# controller.net
KiCad netlist of a schematic drawn in EAGLE
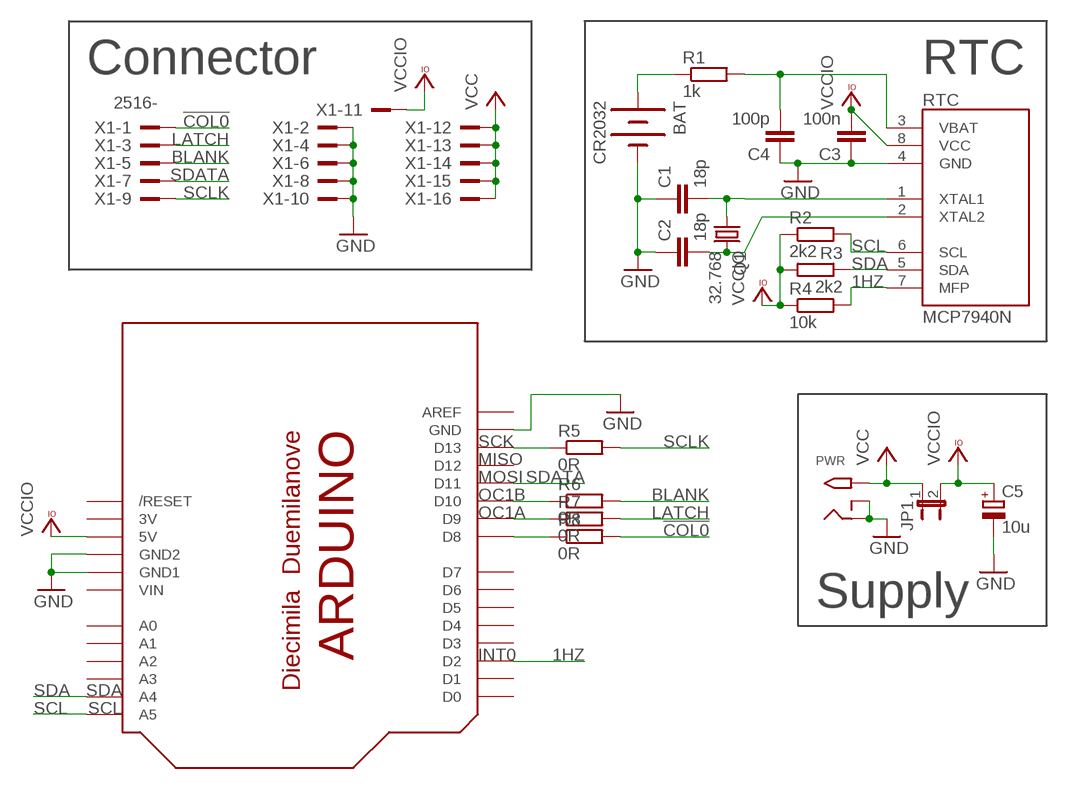
[diagram p0: schematic, sheet 1]

(export (version "E")
  (design (tool "Eeschema 10.0.6"))
  (components
    (comp (ref "ARDU")
      (value "ARDUINODUEMILANOVE")
      (footprint "eagle-import:ARDUINO")
      (libsource (lib "eagle-import") (part "ARDUINODUEMILANOVE"))
    )
    (comp (ref "BAT")
      (value "CR2032")
      (footprint "eagle-import:HAR-S8421")
      (libsource (lib "eagle-import") (part "CR2032"))
    )
    (comp (ref "C1")
      (value "18p")
      (footprint "eagle-import:C0603")
      (libsource (lib "eagle-import") (part "C-EUC0603"))
    )
    (comp (ref "C2")
      (value "18p")
      (footprint "eagle-import:C0603")
      (libsource (lib "eagle-import") (part "C-EUC0603"))
    )
    (comp (ref "C3")
      (value "100n")
      (footprint "eagle-import:C0603K")
      (libsource (lib "eagle-import") (part "C-EUC0603K"))
    )
    (comp (ref "C4")
      (value "100p")
      (footprint "eagle-import:C0603")
      (libsource (lib "eagle-import") (part "C-EUC0603"))
    )
    (comp (ref "C5")
      (value "10u")
      (footprint "eagle-import:C_6032-28R")
      (libsource (lib "eagle-import") (part "CPOL-EUC/6032-28R"))
    )
    (comp (ref "JP1")
      (value "JP1E")
      (footprint "eagle-import:JP1")
      (libsource (lib "eagle-import") (part "JP1E"))
    )
    (comp (ref "PWR")
      (value "2.1MMJACKTHM")
      (footprint "eagle-import:PJ-102A")
      (libsource (lib "eagle-import") (part "2.1MMJACKTHM"))
    )
    (comp (ref "Q1")
      (value "32.768")
      (footprint "eagle-import:MM20SS")
      (libsource (lib "eagle-import") (part "CRYSTALMM20SS"))
    )
    (comp (ref "R1")
      (value "1k")
      (footprint "eagle-import:R0603")
      (libsource (lib "eagle-import") (part "R-EU_R0603"))
    )
    (comp (ref "R2")
      (value "2k2")
      (footprint "eagle-import:R0603")
      (libsource (lib "eagle-import") (part "R-EU_R0603"))
    )
    (comp (ref "R3")
      (value "2k2")
      (footprint "eagle-import:R0603")
      (libsource (lib "eagle-import") (part "R-EU_R0603"))
    )
    (comp (ref "R4")
      (value "10k")
      (footprint "eagle-import:R0603")
      (libsource (lib "eagle-import") (part "R-EU_R0603"))
    )
    (comp (ref "R5")
      (value "0R")
      (footprint "eagle-import:R0603")
      (libsource (lib "eagle-import") (part "R-EU_R0603"))
    )
    (comp (ref "R6")
      (value "0R")
      (footprint "eagle-import:R0603")
      (libsource (lib "eagle-import") (part "R-EU_R0603"))
    )
    (comp (ref "R7")
      (value "0R")
      (footprint "eagle-import:R0603")
      (libsource (lib "eagle-import") (part "R-EU_R0603"))
    )
    (comp (ref "R8")
      (value "0R")
      (footprint "eagle-import:R0603")
      (libsource (lib "eagle-import") (part "R-EU_R0603"))
    )
    (comp (ref "RTC")
      (value "MCP7940N")
      (footprint "eagle-import:SO08")
      (libsource (lib "eagle-import") (part "MCP7940N"))
    )
    (comp (ref "X1")
      (value "2516-")
      (footprint "eagle-import:PAK100_2500-16")
      (libsource (lib "eagle-import") (part "2516-"))
    )
  )
  (nets
    (net (code "1") (name "/1HZ") (class "Default")
      (node (ref "ARDU") (pin "D2") (pinfunction "D2_D2") (pintype "bidirectional"))
      (node (ref "R4") (pin "2") (pinfunction "2_2") (pintype "passive"))
      (node (ref "RTC") (pin "7") (pinfunction "MFP_7") (pintype "bidirectional"))
    )
    (net (code "2") (name "/3V") (class "Default")
      (node (ref "ARDU") (pin "3V") (pinfunction "3V_3V") (pintype "power_in"))
    )
    (net (code "3") (name "/BLANK") (class "Default")
      (node (ref "R6") (pin "2") (pinfunction "2_2") (pintype "passive"))
      (node (ref "X1") (pin "5") (pinfunction "KL_5") (pintype "passive"))
    )
    (net (code "4") (name "/LATCH") (class "Default")
      (node (ref "R7") (pin "2") (pinfunction "2_2") (pintype "passive"))
      (node (ref "X1") (pin "3") (pinfunction "KL_3") (pintype "passive"))
    )
    (net (code "5") (name "/SCL") (class "Default")
      (node (ref "ARDU") (pin "A5") (pinfunction "A5_A5") (pintype "bidirectional"))
      (node (ref "R2") (pin "2") (pinfunction "2_2") (pintype "passive"))
      (node (ref "RTC") (pin "6") (pinfunction "SCL_6") (pintype "bidirectional"))
    )
    (net (code "6") (name "/SCLK") (class "Default")
      (node (ref "R5") (pin "2") (pinfunction "2_2") (pintype "passive"))
      (node (ref "X1") (pin "9") (pinfunction "KL_9") (pintype "passive"))
    )
    (net (code "7") (name "/SDA") (class "Default")
      (node (ref "ARDU") (pin "A4") (pinfunction "A4_A4") (pintype "bidirectional"))
      (node (ref "R3") (pin "1") (pinfunction "1_1") (pintype "passive"))
      (node (ref "RTC") (pin "5") (pinfunction "SDA_5") (pintype "bidirectional"))
    )
    (net (code "8") (name "/SDATA") (class "Default")
      (node (ref "ARDU") (pin "D11") (pinfunction "D11_D11") (pintype "bidirectional"))
      (node (ref "X1") (pin "7") (pinfunction "KL_7") (pintype "passive"))
    )
    (net (code "9") (name "/VIN") (class "Default")
      (node (ref "ARDU") (pin "VIN") (pinfunction "VIN_VIN") (pintype "power_in"))
    )
    (net (code "10") (name "/~{COL0}") (class "Default")
      (node (ref "R8") (pin "2") (pinfunction "2_2") (pintype "passive"))
      (node (ref "X1") (pin "1") (pinfunction "KL_1") (pintype "passive"))
    )
    (net (code "11") (name "GND") (class "Default")
      (node (ref "ARDU") (pin "GND") (pinfunction "GND_GND") (pintype "power_in"))
      (node (ref "ARDU") (pin "GND1") (pinfunction "GND1_GND1") (pintype "power_in"))
      (node (ref "ARDU") (pin "GND2") (pinfunction "GND2_GND2") (pintype "power_in"))
      (node (ref "BAT") (pin "-") (pinfunction "-_-") (pintype "power_in"))
      (node (ref "C1") (pin "1") (pinfunction "1_1") (pintype "passive"))
      (node (ref "C2") (pin "1") (pinfunction "1_1") (pintype "passive"))
      (node (ref "C3") (pin "1") (pinfunction "1_1") (pintype "passive"))
      (node (ref "C4") (pin "1") (pinfunction "1_1") (pintype "passive"))
      (node (ref "C5") (pin "-") (pinfunction "-_-") (pintype "passive"))
      (node (ref "PWR") (pin "RING") (pinfunction "RING_RING") (pintype "bidirectional"))
      (node (ref "PWR") (pin "RING_SW") (pinfunction "RING_SW_RING_SW") (pintype "bidirectional"))
      (node (ref "RTC") (pin "4") (pinfunction "GND_4") (pintype "bidirectional"))
      (node (ref "X1") (pin "10") (pinfunction "KL_10") (pintype "passive"))
      (node (ref "X1") (pin "2") (pinfunction "KL_2") (pintype "passive"))
      (node (ref "X1") (pin "4") (pinfunction "KL_4") (pintype "passive"))
      (node (ref "X1") (pin "6") (pinfunction "KL_6") (pintype "passive"))
      (node (ref "X1") (pin "8") (pinfunction "KL_8") (pintype "passive"))
    )
    (net (code "12") (name "Net-(ARDU-PadD8)") (class "Default")
      (node (ref "ARDU") (pin "D8") (pinfunction "D8_D8") (pintype "bidirectional"))
      (node (ref "R8") (pin "1") (pinfunction "1_1") (pintype "passive"))
    )
    (net (code "13") (name "Net-(ARDU-PadD9)") (class "Default")
      (node (ref "ARDU") (pin "D9") (pinfunction "D9_D9") (pintype "bidirectional"))
      (node (ref "R7") (pin "1") (pinfunction "1_1") (pintype "passive"))
    )
    (net (code "14") (name "Net-(ARDU-PadD10)") (class "Default")
      (node (ref "ARDU") (pin "D10") (pinfunction "D10_D10") (pintype "bidirectional"))
      (node (ref "R6") (pin "1") (pinfunction "1_1") (pintype "passive"))
    )
    (net (code "15") (name "Net-(ARDU-PadD13)") (class "Default")
      (node (ref "ARDU") (pin "D13") (pinfunction "D13_D13") (pintype "bidirectional"))
      (node (ref "R5") (pin "1") (pinfunction "1_1") (pintype "passive"))
    )
    (net (code "16") (name "Net-(BAT-Pad+)") (class "Default")
      (node (ref "BAT") (pin "+") (pinfunction "+_+") (pintype "power_in"))
      (node (ref "R1") (pin "1") (pinfunction "1_1") (pintype "passive"))
    )
    (net (code "17") (name "Net-(Q1-2)") (class "Default")
      (node (ref "C2") (pin "2") (pinfunction "2_2") (pintype "passive"))
      (node (ref "Q1") (pin "4") (pinfunction "2_4") (pintype "passive"))
      (node (ref "RTC") (pin "2") (pinfunction "XTAL2_2") (pintype "bidirectional"))
    )
    (net (code "18") (name "Net-(RTC-VBAT)") (class "Default")
      (node (ref "C4") (pin "2") (pinfunction "2_2") (pintype "passive"))
      (node (ref "R1") (pin "2") (pinfunction "2_2") (pintype "passive"))
      (node (ref "RTC") (pin "3") (pinfunction "VBAT_3") (pintype "bidirectional"))
    )
    (net (code "19") (name "Net-(RTC-XTAL1)") (class "Default")
      (node (ref "C1") (pin "2") (pinfunction "2_2") (pintype "passive"))
      (node (ref "Q1") (pin "1") (pinfunction "1_1") (pintype "passive"))
      (node (ref "RTC") (pin "1") (pinfunction "XTAL1_1") (pintype "bidirectional"))
    )
    (net (code "20") (name "VCC") (class "Default")
      (node (ref "JP1") (pin "1") (pinfunction "1_1") (pintype "passive"))
      (node (ref "PWR") (pin "TIP") (pinfunction "TIP_TIP") (pintype "bidirectional"))
      (node (ref "X1") (pin "12") (pinfunction "KL_12") (pintype "passive"))
      (node (ref "X1") (pin "13") (pinfunction "KL_13") (pintype "passive"))
      (node (ref "X1") (pin "14") (pinfunction "KL_14") (pintype "passive"))
      (node (ref "X1") (pin "15") (pinfunction "KL_15") (pintype "passive"))
      (node (ref "X1") (pin "16") (pinfunction "KL_16") (pintype "passive"))
    )
    (net (code "21") (name "VCCIO") (class "Default")
      (node (ref "ARDU") (pin "5V") (pinfunction "5V_5V") (pintype "power_in"))
      (node (ref "C3") (pin "2") (pinfunction "2_2") (pintype "passive"))
      (node (ref "C5") (pin "+") (pinfunction "+_+") (pintype "passive"))
      (node (ref "JP1") (pin "2") (pinfunction "2_2") (pintype "passive"))
      (node (ref "R2") (pin "1") (pinfunction "1_1") (pintype "passive"))
      (node (ref "R3") (pin "2") (pinfunction "2_2") (pintype "passive"))
      (node (ref "R4") (pin "1") (pinfunction "1_1") (pintype "passive"))
      (node (ref "RTC") (pin "8") (pinfunction "VCC_8") (pintype "bidirectional"))
      (node (ref "X1") (pin "11") (pinfunction "KL_11") (pintype "passive"))
    )
    (net (code "22") (name "unconnected-(ARDU-PadA0)") (class "Default")
      (node (ref "ARDU") (pin "A0") (pinfunction "A0_A0") (pintype "bidirectional"))
    )
    (net (code "23") (name "unconnected-(ARDU-PadA1)") (class "Default")
      (node (ref "ARDU") (pin "A1") (pinfunction "A1_A1") (pintype "bidirectional"))
    )
    (net (code "24") (name "unconnected-(ARDU-PadA2)") (class "Default")
      (node (ref "ARDU") (pin "A2") (pinfunction "A2_A2") (pintype "bidirectional"))
    )
    (net (code "25") (name "unconnected-(ARDU-PadA3)") (class "Default")
      (node (ref "ARDU") (pin "A3") (pinfunction "A3_A3") (pintype "bidirectional"))
    )
    (net (code "26") (name "unconnected-(ARDU-PadAREF)") (class "Default")
      (node (ref "ARDU") (pin "AREF") (pinfunction "AREF_AREF") (pintype "bidirectional"))
    )
    (net (code "27") (name "unconnected-(ARDU-PadD0)") (class "Default")
      (node (ref "ARDU") (pin "D0") (pinfunction "D0_D0") (pintype "bidirectional"))
    )
    (net (code "28") (name "unconnected-(ARDU-PadD1)") (class "Default")
      (node (ref "ARDU") (pin "D1") (pinfunction "D1_D1") (pintype "bidirectional"))
    )
    (net (code "29") (name "unconnected-(ARDU-PadD3)") (class "Default")
      (node (ref "ARDU") (pin "D3") (pinfunction "D3_D3") (pintype "bidirectional"))
    )
    (net (code "30") (name "unconnected-(ARDU-PadD4)") (class "Default")
      (node (ref "ARDU") (pin "D4") (pinfunction "D4_D4") (pintype "bidirectional"))
    )
    (net (code "31") (name "unconnected-(ARDU-PadD5)") (class "Default")
      (node (ref "ARDU") (pin "D5") (pinfunction "D5_D5") (pintype "bidirectional"))
    )
    (net (code "32") (name "unconnected-(ARDU-PadD6)") (class "Default")
      (node (ref "ARDU") (pin "D6") (pinfunction "D6_D6") (pintype "bidirectional"))
    )
    (net (code "33") (name "unconnected-(ARDU-PadD7)") (class "Default")
      (node (ref "ARDU") (pin "D7") (pinfunction "D7_D7") (pintype "bidirectional"))
    )
    (net (code "34") (name "unconnected-(ARDU-PadD12)") (class "Default")
      (node (ref "ARDU") (pin "D12") (pinfunction "D12_D12") (pintype "bidirectional"))
    )
    (net (code "35") (name "unconnected-(ARDU-{slash}RESET-PadRESET)") (class "Default")
      (node (ref "ARDU") (pin "RESET") (pinfunction "/RESET_RESET") (pintype "bidirectional"))
    )
  )
)
